# small_button_panel.net
KiCad netlist of a schematic drawn in EAGLE
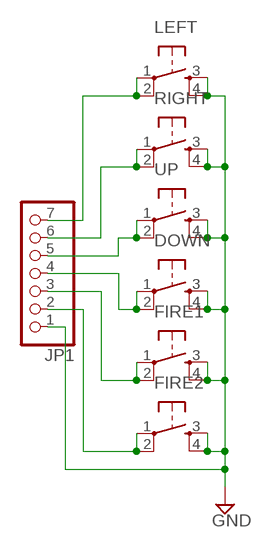
[diagram p0: schematic, sheet 1]

(export (version "E")
  (design (tool "Eeschema 10.0.6"))
  (components
    (comp (ref "DOWN")
      (value "TAC_SWITCHPTH")
      (footprint "eagle-import:TACTILE-PTH")
      (libsource (lib "eagle-import") (part "TAC_SWITCHPTH"))
    )
    (comp (ref "FIRE1")
      (value "TAC_SWITCHPTH")
      (footprint "eagle-import:TACTILE-PTH")
      (libsource (lib "eagle-import") (part "TAC_SWITCHPTH"))
    )
    (comp (ref "FIRE2")
      (value "TAC_SWITCHPTH")
      (footprint "eagle-import:TACTILE-PTH")
      (libsource (lib "eagle-import") (part "TAC_SWITCHPTH"))
    )
    (comp (ref "JP1")
      (value "PINHD-1X7")
      (footprint "eagle-import:1X07")
      (libsource (lib "eagle-import") (part "PINHD-1X7"))
    )
    (comp (ref "LEFT")
      (value "TAC_SWITCHPTH")
      (footprint "eagle-import:TACTILE-PTH")
      (libsource (lib "eagle-import") (part "TAC_SWITCHPTH"))
    )
    (comp (ref "RIGHT")
      (value "TAC_SWITCHPTH")
      (footprint "eagle-import:TACTILE-PTH")
      (libsource (lib "eagle-import") (part "TAC_SWITCHPTH"))
    )
    (comp (ref "UP")
      (value "TAC_SWITCHPTH")
      (footprint "eagle-import:TACTILE-PTH")
      (libsource (lib "eagle-import") (part "TAC_SWITCHPTH"))
    )
  )
  (nets
    (net (code "1") (name "GND") (class "Default")
      (node (ref "DOWN") (pin "3") (pinfunction "3_3") (pintype "passive"))
      (node (ref "DOWN") (pin "4") (pinfunction "4_4") (pintype "passive"))
      (node (ref "FIRE1") (pin "3") (pinfunction "3_3") (pintype "passive"))
      (node (ref "FIRE1") (pin "4") (pinfunction "4_4") (pintype "passive"))
      (node (ref "FIRE2") (pin "3") (pinfunction "3_3") (pintype "passive"))
      (node (ref "FIRE2") (pin "4") (pinfunction "4_4") (pintype "passive"))
      (node (ref "JP1") (pin "1") (pinfunction "1_1") (pintype "passive"))
      (node (ref "LEFT") (pin "3") (pinfunction "3_3") (pintype "passive"))
      (node (ref "LEFT") (pin "4") (pinfunction "4_4") (pintype "passive"))
      (node (ref "RIGHT") (pin "3") (pinfunction "3_3") (pintype "passive"))
      (node (ref "RIGHT") (pin "4") (pinfunction "4_4") (pintype "passive"))
      (node (ref "UP") (pin "3") (pinfunction "3_3") (pintype "passive"))
      (node (ref "UP") (pin "4") (pinfunction "4_4") (pintype "passive"))
    )
    (net (code "2") (name "Net-(DOWN-Pad1)") (class "Default")
      (node (ref "DOWN") (pin "1") (pinfunction "1_1") (pintype "passive"))
      (node (ref "DOWN") (pin "2") (pinfunction "2_2") (pintype "passive"))
      (node (ref "JP1") (pin "4") (pinfunction "4_4") (pintype "passive"))
    )
    (net (code "3") (name "Net-(FIRE1-Pad1)") (class "Default")
      (node (ref "FIRE1") (pin "1") (pinfunction "1_1") (pintype "passive"))
      (node (ref "FIRE1") (pin "2") (pinfunction "2_2") (pintype "passive"))
      (node (ref "JP1") (pin "3") (pinfunction "3_3") (pintype "passive"))
    )
    (net (code "4") (name "Net-(FIRE2-Pad1)") (class "Default")
      (node (ref "FIRE2") (pin "1") (pinfunction "1_1") (pintype "passive"))
      (node (ref "FIRE2") (pin "2") (pinfunction "2_2") (pintype "passive"))
      (node (ref "JP1") (pin "2") (pinfunction "2_2") (pintype "passive"))
    )
    (net (code "5") (name "Net-(JP1-Pad5)") (class "Default")
      (node (ref "JP1") (pin "5") (pinfunction "5_5") (pintype "passive"))
      (node (ref "UP") (pin "1") (pinfunction "1_1") (pintype "passive"))
      (node (ref "UP") (pin "2") (pinfunction "2_2") (pintype "passive"))
    )
    (net (code "6") (name "Net-(JP1-Pad6)") (class "Default")
      (node (ref "JP1") (pin "6") (pinfunction "6_6") (pintype "passive"))
      (node (ref "RIGHT") (pin "1") (pinfunction "1_1") (pintype "passive"))
      (node (ref "RIGHT") (pin "2") (pinfunction "2_2") (pintype "passive"))
    )
    (net (code "7") (name "Net-(JP1-Pad7)") (class "Default")
      (node (ref "JP1") (pin "7") (pinfunction "7_7") (pintype "passive"))
      (node (ref "LEFT") (pin "1") (pinfunction "1_1") (pintype "passive"))
      (node (ref "LEFT") (pin "2") (pinfunction "2_2") (pintype "passive"))
    )
  )
)
